# AnalogDaisy.net
KiCad netlist of a schematic drawn in EAGLE
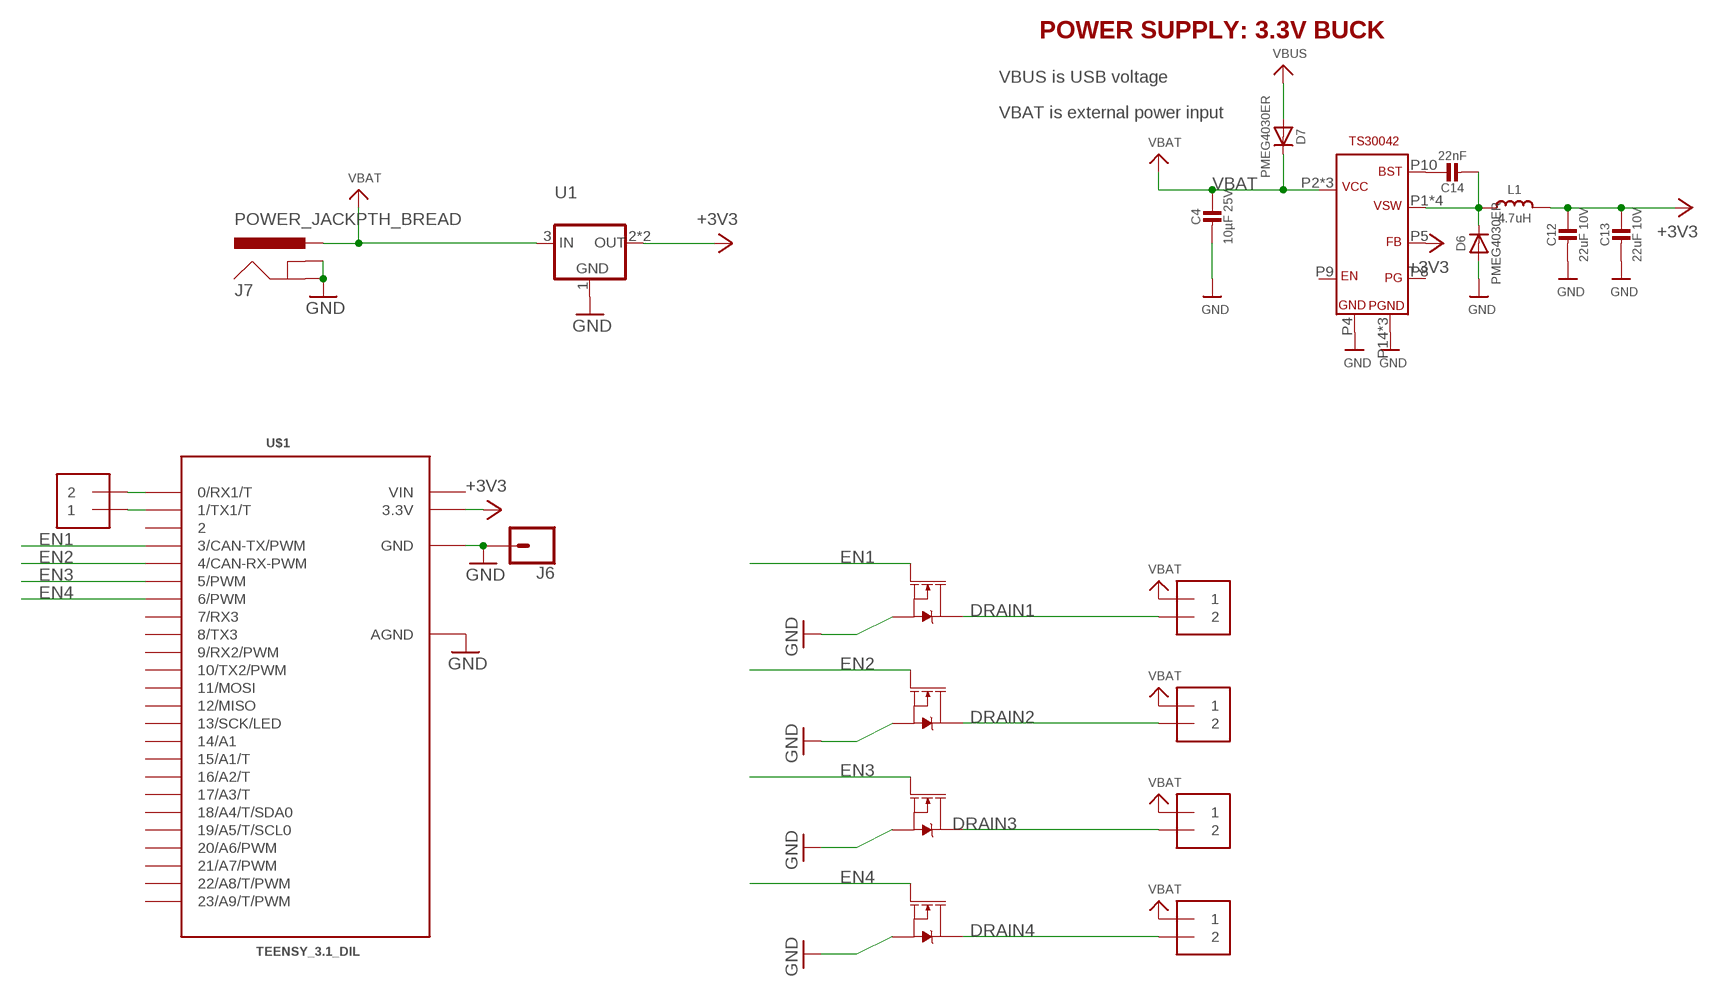
[diagram p0: schematic, sheet 1]

(export (version "E")
  (design (tool "Eeschema 10.0.6"))
  (components
    (comp (ref "C4")
      (value "10µF 25V")
      (footprint "eagle-import:0603-MINI")
      (libsource (lib "eagle-import") (part "CAP_CERAMIC0603MINI"))
    )
    (comp (ref "C12")
      (value "22uF 10V")
      (footprint "eagle-import:0603-MINI")
      (libsource (lib "eagle-import") (part "CAP_CERAMIC0603MINI"))
    )
    (comp (ref "C13")
      (value "22uF 10V")
      (footprint "eagle-import:0603-MINI")
      (libsource (lib "eagle-import") (part "CAP_CERAMIC0603MINI"))
    )
    (comp (ref "C14")
      (value "22nF")
      (footprint "eagle-import:0603-MINI")
      (libsource (lib "eagle-import") (part "CAP_CERAMIC0603MINI"))
    )
    (comp (ref "D6")
      (value "PMEG4030ER")
      (footprint "eagle-import:SOD-123")
      (libsource (lib "eagle-import") (part "DIODESOD-123"))
    )
    (comp (ref "D7")
      (value "PMEG4030ER")
      (footprint "eagle-import:SOD-123")
      (libsource (lib "eagle-import") (part "DIODESOD-123"))
    )
    (comp (ref "J1")
      (value "1X2-3.5MM")
      (footprint "eagle-import:1X2-3.5MM")
      (libsource (lib "eagle-import") (part "1X2-3.5MM"))
    )
    (comp (ref "J2")
      (value "1X2-3.5MM")
      (footprint "eagle-import:1X2-3.5MM")
      (libsource (lib "eagle-import") (part "1X2-3.5MM"))
    )
    (comp (ref "J3")
      (value "1X2-3.5MM")
      (footprint "eagle-import:1X2-3.5MM")
      (libsource (lib "eagle-import") (part "1X2-3.5MM"))
    )
    (comp (ref "J4")
      (value "1X2-3.5MM")
      (footprint "eagle-import:1X2-3.5MM")
      (libsource (lib "eagle-import") (part "1X2-3.5MM"))
    )
    (comp (ref "J5")
      (value "1X2-3.5MM")
      (footprint "eagle-import:1X2-3.5MM")
      (libsource (lib "eagle-import") (part "1X2-3.5MM"))
    )
    (comp (ref "J6")
      (value "CONN_01")
      (footprint "eagle-import:1X01")
      (libsource (lib "eagle-import") (part "CONN_01"))
    )
    (comp (ref "J7")
      (value "POWER_JACKPTH_BREAD")
      (footprint "eagle-import:POWER_JACK_PTH_BREAD")
      (libsource (lib "eagle-import") (part "POWER_JACKPTH_BREAD"))
    )
    (comp (ref "L1")
      (value "4.7uH")
      (footprint "eagle-import:INDUCTOR_5X5MM_TDK_VLC5045")
      (libsource (lib "eagle-import") (part "INDUCTORTDK_VLC5045"))
    )
    (comp (ref "Q1")
      (value "35A/25V/8.5mΩ")
      (footprint "eagle-import:DPAK")
      (libsource (lib "eagle-import") (part "MOSFET-NCH-FDD8780"))
    )
    (comp (ref "Q3")
      (value "35A/25V/8.5mΩ")
      (footprint "eagle-import:DPAK")
      (libsource (lib "eagle-import") (part "MOSFET-NCH-FDD8780"))
    )
    (comp (ref "Q5")
      (value "35A/25V/8.5mΩ")
      (footprint "eagle-import:DPAK")
      (libsource (lib "eagle-import") (part "MOSFET-NCH-FDD8780"))
    )
    (comp (ref "Q6")
      (value "35A/25V/8.5mΩ")
      (footprint "eagle-import:DPAK")
      (libsource (lib "eagle-import") (part "MOSFET-NCH-FDD8780"))
    )
    (comp (ref "U$1")
      (value "TEENSY_3.1_DIL")
      (footprint "eagle-import:TEENSY3-DIL")
      (libsource (lib "eagle-import") (part "TEENSY_3.1_DIL"))
    )
    (comp (ref "U$19")
      (value "BUCK_CONVERTER")
      (footprint "eagle-import:QFN-16")
      (libsource (lib "eagle-import") (part "BUCK_CONVERTER"))
    )
    (comp (ref "U1")
      (value "VREG_SOT223")
      (footprint "eagle-import:SOT223-R")
      (libsource (lib "eagle-import") (part "VREG_SOT223"))
    )
  )
  (nets
    (net (code "1") (name "+3V3") (class "Default")
      (node (ref "C12") (pin "1") (pinfunction "1_1") (pintype "passive"))
      (node (ref "C13") (pin "1") (pinfunction "1_1") (pintype "passive"))
      (node (ref "L1") (pin "P$2") (pinfunction "2_P$2") (pintype "passive"))
      (node (ref "U$1") (pin "3.3V") (pinfunction "3.3V_3.3V") (pintype "power_in"))
      (node (ref "U$19") (pin "P5") (pinfunction "FB_P5") (pintype "bidirectional"))
      (node (ref "U1") (pin "2") (pinfunction "OUT_2") (pintype "power_in"))
      (node (ref "U1") (pin "4") (pinfunction "OUT_4") (pintype "power_in"))
    )
    (net (code "2") (name "/DRAIN1") (class "Default")
      (node (ref "J2") (pin "2") (pinfunction "2_2") (pintype "passive"))
      (node (ref "Q1") (pin "4") (pinfunction "D_4") (pintype "bidirectional"))
    )
    (net (code "3") (name "/DRAIN2") (class "Default")
      (node (ref "J3") (pin "2") (pinfunction "2_2") (pintype "passive"))
      (node (ref "Q3") (pin "4") (pinfunction "D_4") (pintype "bidirectional"))
    )
    (net (code "4") (name "/DRAIN3") (class "Default")
      (node (ref "J4") (pin "2") (pinfunction "2_2") (pintype "passive"))
      (node (ref "Q5") (pin "4") (pinfunction "D_4") (pintype "bidirectional"))
    )
    (net (code "5") (name "/DRAIN4") (class "Default")
      (node (ref "J5") (pin "2") (pinfunction "2_2") (pintype "passive"))
      (node (ref "Q6") (pin "4") (pinfunction "D_4") (pintype "bidirectional"))
    )
    (net (code "6") (name "/EN1") (class "Default")
      (node (ref "Q1") (pin "1") (pinfunction "G_1") (pintype "bidirectional"))
      (node (ref "U$1") (pin "3") (pinfunction "3/CAN-TX/PWM_3") (pintype "bidirectional"))
    )
    (net (code "7") (name "/EN2") (class "Default")
      (node (ref "Q3") (pin "1") (pinfunction "G_1") (pintype "bidirectional"))
      (node (ref "U$1") (pin "4") (pinfunction "4/CAN-RX-PWM_4") (pintype "bidirectional"))
    )
    (net (code "8") (name "/EN3") (class "Default")
      (node (ref "Q5") (pin "1") (pinfunction "G_1") (pintype "bidirectional"))
      (node (ref "U$1") (pin "5") (pinfunction "5/PWM_5") (pintype "bidirectional"))
    )
    (net (code "9") (name "/EN4") (class "Default")
      (node (ref "Q6") (pin "1") (pinfunction "G_1") (pintype "bidirectional"))
      (node (ref "U$1") (pin "6") (pinfunction "6/PWM_6") (pintype "bidirectional"))
    )
    (net (code "10") (name "/VIN") (class "Default")
      (node (ref "U$1") (pin "VIN") (pinfunction "VIN_VIN") (pintype "power_in"))
    )
    (net (code "11") (name "GND") (class "Default")
      (node (ref "C12") (pin "2") (pinfunction "2_2") (pintype "passive"))
      (node (ref "C13") (pin "2") (pinfunction "2_2") (pintype "passive"))
      (node (ref "C4") (pin "2") (pinfunction "2_2") (pintype "passive"))
      (node (ref "D6") (pin "A") (pinfunction "A_A") (pintype "passive"))
      (node (ref "J6") (pin "1") (pinfunction "1_1") (pintype "passive"))
      (node (ref "J7") (pin "GND") (pinfunction "GND_GND") (pintype "bidirectional"))
      (node (ref "J7") (pin "GNDBREAK") (pinfunction "GNDBREAK_GNDBREAK") (pintype "bidirectional"))
      (node (ref "Q1") (pin "3") (pinfunction "S_3") (pintype "bidirectional"))
      (node (ref "Q3") (pin "3") (pinfunction "S_3") (pintype "bidirectional"))
      (node (ref "Q5") (pin "3") (pinfunction "S_3") (pintype "bidirectional"))
      (node (ref "Q6") (pin "3") (pinfunction "S_3") (pintype "bidirectional"))
      (node (ref "U$1") (pin "AGND") (pinfunction "AGND_AGND") (pintype "power_in"))
      (node (ref "U$1") (pin "GND") (pinfunction "GND_GND") (pintype "power_in"))
      (node (ref "U$19") (pin "P14") (pinfunction "PGND_P14") (pintype "bidirectional"))
      (node (ref "U$19") (pin "P15") (pinfunction "PGND_P15") (pintype "bidirectional"))
      (node (ref "U$19") (pin "P4") (pinfunction "GND_P4") (pintype "bidirectional"))
      (node (ref "U$19") (pin "PAD") (pinfunction "PGND_PAD") (pintype "bidirectional"))
      (node (ref "U1") (pin "1") (pinfunction "GND_1") (pintype "power_in"))
    )
    (net (code "12") (name "Net-(L1-1)") (class "Default")
      (node (ref "C14") (pin "2") (pinfunction "2_2") (pintype "passive"))
      (node (ref "D6") (pin "C") (pinfunction "C_C") (pintype "passive"))
      (node (ref "L1") (pin "P$1") (pinfunction "1_P$1") (pintype "passive"))
      (node (ref "U$19") (pin "P1") (pinfunction "VSW_P1") (pintype "bidirectional"))
      (node (ref "U$19") (pin "P12") (pinfunction "VSW_P12") (pintype "bidirectional"))
      (node (ref "U$19") (pin "P13") (pinfunction "VSW_P13") (pintype "bidirectional"))
      (node (ref "U$19") (pin "P16") (pinfunction "VSW_P16") (pintype "bidirectional"))
    )
    (net (code "13") (name "Net-(U$1-0{slash}RX1{slash}T)") (class "Default")
      (node (ref "J1") (pin "2") (pinfunction "2_2") (pintype "passive"))
      (node (ref "U$1") (pin "0") (pinfunction "0/RX1/T_0") (pintype "bidirectional"))
    )
    (net (code "14") (name "Net-(U$1-1{slash}TX1{slash}T)") (class "Default")
      (node (ref "J1") (pin "1") (pinfunction "1_1") (pintype "passive"))
      (node (ref "U$1") (pin "1") (pinfunction "1/TX1/T_1") (pintype "bidirectional"))
    )
    (net (code "15") (name "Net-(U$19-BST)") (class "Default")
      (node (ref "C14") (pin "1") (pinfunction "1_1") (pintype "passive"))
      (node (ref "U$19") (pin "P10") (pinfunction "BST_P10") (pintype "bidirectional"))
    )
    (net (code "16") (name "VBAT") (class "Default")
      (node (ref "C4") (pin "1") (pinfunction "1_1") (pintype "passive"))
      (node (ref "D7") (pin "C") (pinfunction "C_C") (pintype "passive"))
      (node (ref "J2") (pin "1") (pinfunction "1_1") (pintype "passive"))
      (node (ref "J3") (pin "1") (pinfunction "1_1") (pintype "passive"))
      (node (ref "J4") (pin "1") (pinfunction "1_1") (pintype "passive"))
      (node (ref "J5") (pin "1") (pinfunction "1_1") (pintype "passive"))
      (node (ref "J7") (pin "PWR") (pinfunction "PWR_PWR") (pintype "bidirectional"))
      (node (ref "U$19") (pin "P11") (pinfunction "VCC_P11") (pintype "bidirectional"))
      (node (ref "U$19") (pin "P2") (pinfunction "VCC_P2") (pintype "bidirectional"))
      (node (ref "U$19") (pin "P3") (pinfunction "VCC_P3") (pintype "bidirectional"))
      (node (ref "U1") (pin "3") (pinfunction "IN_3") (pintype "power_in"))
    )
    (net (code "17") (name "VBUS") (class "Default")
      (node (ref "D7") (pin "A") (pinfunction "A_A") (pintype "passive"))
    )
    (net (code "18") (name "unconnected-(U$1-7{slash}RX3-Pad7)") (class "Default")
      (node (ref "U$1") (pin "7") (pinfunction "7/RX3_7") (pintype "bidirectional"))
    )
    (net (code "19") (name "unconnected-(U$1-8{slash}TX3-Pad8)") (class "Default")
      (node (ref "U$1") (pin "8") (pinfunction "8/TX3_8") (pintype "bidirectional"))
    )
    (net (code "20") (name "unconnected-(U$1-9{slash}RX2{slash}PWM-Pad9)") (class "Default")
      (node (ref "U$1") (pin "9") (pinfunction "9/RX2/PWM_9") (pintype "bidirectional"))
    )
    (net (code "21") (name "unconnected-(U$1-10{slash}TX2{slash}PWM-Pad10)") (class "Default")
      (node (ref "U$1") (pin "10") (pinfunction "10/TX2/PWM_10") (pintype "bidirectional"))
    )
    (net (code "22") (name "unconnected-(U$1-11{slash}MOSI-Pad11)") (class "Default")
      (node (ref "U$1") (pin "11") (pinfunction "11/MOSI_11") (pintype "bidirectional"))
    )
    (net (code "23") (name "unconnected-(U$1-12{slash}MISO-Pad12)") (class "Default")
      (node (ref "U$1") (pin "12") (pinfunction "12/MISO_12") (pintype "bidirectional"))
    )
    (net (code "24") (name "unconnected-(U$1-13{slash}SCK{slash}LED-Pad13)") (class "Default")
      (node (ref "U$1") (pin "13") (pinfunction "13/SCK/LED_13") (pintype "bidirectional"))
    )
    (net (code "25") (name "unconnected-(U$1-14{slash}A1-Pad14{slash}A0)") (class "Default")
      (node (ref "U$1") (pin "14/A0") (pinfunction "14/A1_14/A0") (pintype "bidirectional"))
    )
    (net (code "26") (name "unconnected-(U$1-15{slash}A1{slash}T-Pad15{slash}A1)") (class "Default")
      (node (ref "U$1") (pin "15/A1") (pinfunction "15/A1/T_15/A1") (pintype "bidirectional"))
    )
    (net (code "27") (name "unconnected-(U$1-16{slash}A2{slash}T-Pad16{slash}A2)") (class "Default")
      (node (ref "U$1") (pin "16/A2") (pinfunction "16/A2/T_16/A2") (pintype "bidirectional"))
    )
    (net (code "28") (name "unconnected-(U$1-17{slash}A3{slash}T-Pad17{slash}A3)") (class "Default")
      (node (ref "U$1") (pin "17/A3") (pinfunction "17/A3/T_17/A3") (pintype "bidirectional"))
    )
    (net (code "29") (name "unconnected-(U$1-18{slash}A4{slash}T{slash}SDA0-Pad18{slash}A4)") (class "Default")
      (node (ref "U$1") (pin "18/A4") (pinfunction "18/A4/T/SDA0_18/A4") (pintype "bidirectional"))
    )
    (net (code "30") (name "unconnected-(U$1-19{slash}A5{slash}T{slash}SCL0-Pad19{slash}A5)") (class "Default")
      (node (ref "U$1") (pin "19/A5") (pinfunction "19/A5/T/SCL0_19/A5") (pintype "bidirectional"))
    )
    (net (code "31") (name "unconnected-(U$1-20{slash}A6{slash}PWM-Pad20{slash}A6)") (class "Default")
      (node (ref "U$1") (pin "20/A6") (pinfunction "20/A6/PWM_20/A6") (pintype "bidirectional"))
    )
    (net (code "32") (name "unconnected-(U$1-21{slash}A7{slash}PWM-Pad21{slash}A7)") (class "Default")
      (node (ref "U$1") (pin "21/A7") (pinfunction "21/A7/PWM_21/A7") (pintype "bidirectional"))
    )
    (net (code "33") (name "unconnected-(U$1-22{slash}A8{slash}T{slash}PWM-Pad22{slash}A8)") (class "Default")
      (node (ref "U$1") (pin "22/A8") (pinfunction "22/A8/T/PWM_22/A8") (pintype "bidirectional"))
    )
    (net (code "34") (name "unconnected-(U$1-23{slash}A9{slash}T{slash}PWM-Pad23{slash}A9)") (class "Default")
      (node (ref "U$1") (pin "23/A9") (pinfunction "23/A9/T/PWM_23/A9") (pintype "bidirectional"))
    )
    (net (code "35") (name "unconnected-(U$1-Pad2)") (class "Default")
      (node (ref "U$1") (pin "2") (pinfunction "2_2") (pintype "bidirectional"))
    )
    (net (code "36") (name "unconnected-(U$19-EN-PadP9)") (class "Default")
      (node (ref "U$19") (pin "P9") (pinfunction "EN_P9") (pintype "bidirectional"))
    )
    (net (code "37") (name "unconnected-(U$19-PG-PadP8)") (class "Default")
      (node (ref "U$19") (pin "P8") (pinfunction "PG_P8") (pintype "bidirectional"))
    )
  )
)
